# Nakuja.net
KiCad netlist of a schematic drawn in EasyEDA
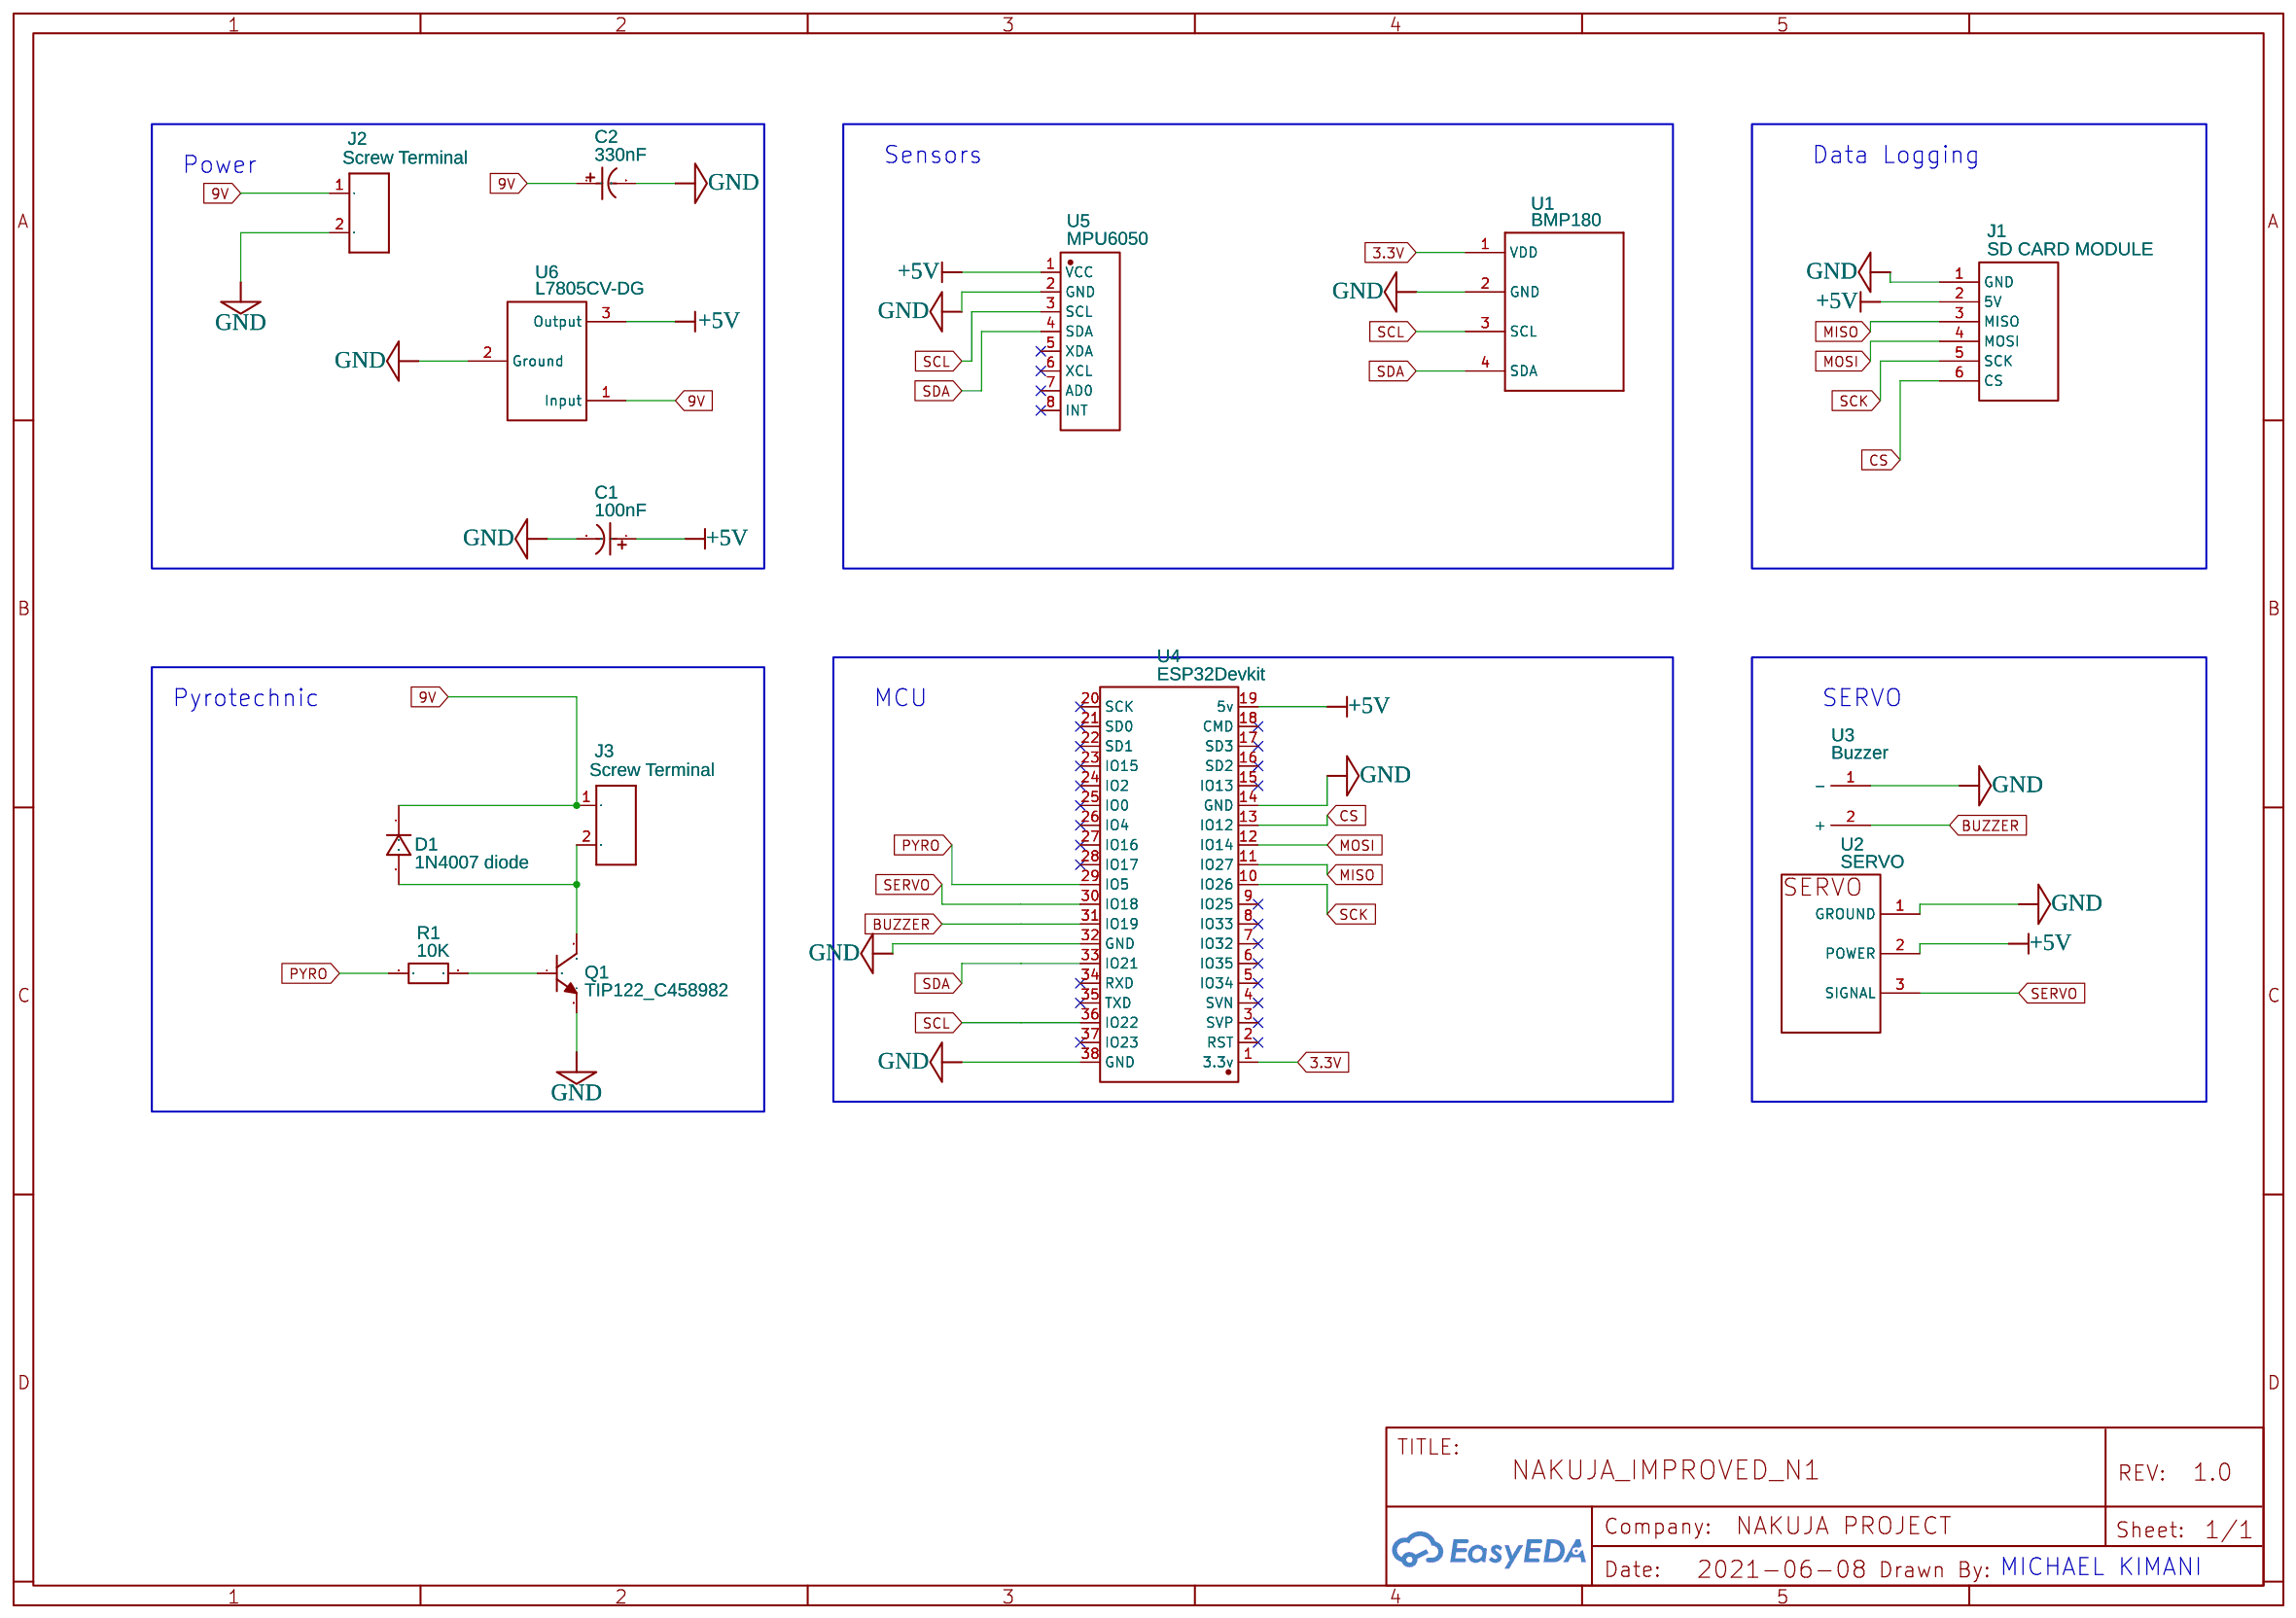
[diagram p0: schematic sheet]

(export (version "E")
  (design (tool "Eeschema 10.0.6"))
  (components
    (comp (ref "C1")
      (value "100nF")
      (fields (field (name "BOM_Manufacturer Part") "0.1UF 50V") (field (name "BOM_Supplier Part") "C28061"))
      (libsource (lib "") (part "0.1UF 50V"))
    )
    (comp (ref "C2")
      (value "330nF")
      (fields
        (field (name "BOM_Manufacturer Part") "0.33uF 50V 5*11")
        (field (name "BOM_Supplier Part") "C45097")
      )
      (libsource (lib "") (part "0.33uF 50V 5*11"))
    )
    (comp (ref "D1")
      (value "1N4007 diode")
      (fields (field (name "BOM_Manufacturer Part") "1N4007") (field (name "BOM_Supplier Part") "C331633"))
      (libsource (lib "") (part "1N4007 diode"))
    )
    (comp (ref "J1")
      (value "SD CARD MODULE")
      (fields (field (name "BOM_Manufacturer Part") "GREATZT 1pcs Micro SD card mini TF card reader module"))
      (libsource (lib "") (part "SD CARD MODULE"))
    )
    (comp (ref "J2")
      (value "Screw Terminal")
      (fields (field (name "BOM_Manufacturer Part") "?"))
      (libsource (lib "") (part "Screw Terminal"))
    )
    (comp (ref "J3")
      (value "Screw Terminal")
      (fields (field (name "BOM_Manufacturer Part") "?"))
      (libsource (lib "") (part "Screw Terminal"))
    )
    (comp (ref "Q1")
      (value "TIP122_C458982")
      (fields (field (name "BOM_Manufacturer Part") "TIP122") (field (name "BOM_Supplier Part") "C458982"))
      (libsource (lib "") (part "TIP122_C458982"))
    )
    (comp (ref "R1")
      (value "10K")
      (fields
        (field (name "BOM_Manufacturer Part") "RN 1/8W 10K F T/B A1")
        (field (name "BOM_Supplier Part") "C433502")
      )
      (libsource (lib "") (part "RN 1/8W 10K F T/B A1"))
    )
    (comp (ref "U1") (value "BMP180") (libsource (lib "") (part "BMP180")))
    (comp (ref "U2") (value "SERVO") (libsource (lib "") (part "SERVO")))
    (comp (ref "U3") (value "Buzzer") (libsource (lib "") (part "Buzzer")))
    (comp (ref "U4") (value "ESP32Devkit") (libsource (lib "") (part "ESP32Devkit")))
    (comp (ref "U5") (value "MPU6050") (libsource (lib "") (part "MPU6050")))
    (comp (ref "U6")
      (value "L7805CV-DG")
      (fields (field (name "BOM_Supplier Part") "C3795"))
      (libsource (lib "") (part "L7805CV-DG"))
    )
  )
  (nets
    (net (code "1") (name "+5V") (class "Default")
      (node (ref "C1") (pin "1") (pinfunction "1_1") (pintype "input"))
      (node (ref "J1") (pin "2") (pinfunction "5V_2") (pintype "unspecified"))
      (node (ref "U2") (pin "2") (pinfunction "POWER_2") (pintype "unspecified"))
      (node (ref "U4") (pin "19") (pinfunction "5v_19") (pintype "unspecified"))
      (node (ref "U5") (pin "1") (pinfunction "VCC_1") (pintype "unspecified"))
      (node (ref "U6") (pin "3") (pinfunction "Output_3") (pintype "unspecified"))
    )
    (net (code "2") (name "3.3V") (class "Default")
      (node (ref "U1") (pin "1") (pinfunction "VDD_1") (pintype "passive"))
      (node (ref "U4") (pin "1") (pinfunction "3.3v_1") (pintype "unspecified"))
    )
    (net (code "3") (name "9V") (class "Default")
      (node (ref "C2") (pin "1") (pinfunction "1_1") (pintype "input"))
      (node (ref "D1") (pin "1") (pinfunction "1_1") (pintype "unspecified"))
      (node (ref "J2") (pin "1") (pinfunction "1_1") (pintype "unspecified"))
      (node (ref "J3") (pin "1") (pinfunction "1_1") (pintype "unspecified"))
      (node (ref "U6") (pin "1") (pinfunction "Input_1") (pintype "unspecified"))
    )
    (net (code "4") (name "BUZZER") (class "Default")
      (node (ref "U3") (pin "2") (pinfunction "+_2") (pintype "unspecified"))
      (node (ref "U4") (pin "31") (pinfunction "IO19_31") (pintype "unspecified"))
    )
    (net (code "5") (name "CS") (class "Default")
      (node (ref "J1") (pin "6") (pinfunction "CS_6") (pintype "unspecified"))
      (node (ref "U4") (pin "13") (pinfunction "IO12_13") (pintype "unspecified"))
    )
    (net (code "6") (name "GND") (class "Default")
      (node (ref "C1") (pin "2") (pinfunction "2_2") (pintype "input"))
      (node (ref "C2") (pin "2") (pinfunction "2_2") (pintype "input"))
      (node (ref "J1") (pin "1") (pinfunction "GND_1") (pintype "unspecified"))
      (node (ref "J2") (pin "2") (pinfunction "2_2") (pintype "unspecified"))
      (node (ref "Q1") (pin "3") (pinfunction "E_3") (pintype "unspecified"))
      (node (ref "U1") (pin "2") (pinfunction "GND_2") (pintype "passive"))
      (node (ref "U2") (pin "1") (pinfunction "GROUND_1") (pintype "unspecified"))
      (node (ref "U3") (pin "1") (pinfunction "-_1") (pintype "unspecified"))
      (node (ref "U4") (pin "14") (pinfunction "GND_14") (pintype "unspecified"))
      (node (ref "U4") (pin "32") (pinfunction "GND_32") (pintype "unspecified"))
      (node (ref "U4") (pin "38") (pinfunction "GND_38") (pintype "unspecified"))
      (node (ref "U5") (pin "2") (pinfunction "GND_2") (pintype "unspecified"))
      (node (ref "U6") (pin "2") (pinfunction "Ground_2") (pintype "unspecified"))
    )
    (net (code "7") (name "MISO") (class "Default")
      (node (ref "J1") (pin "3") (pinfunction "MISO_3") (pintype "unspecified"))
      (node (ref "U4") (pin "11") (pinfunction "IO27_11") (pintype "unspecified"))
    )
    (net (code "8") (name "MOSI") (class "Default")
      (node (ref "J1") (pin "4") (pinfunction "MOSI_4") (pintype "unspecified"))
      (node (ref "U4") (pin "12") (pinfunction "IO14_12") (pintype "unspecified"))
    )
    (net (code "9") (name "Net-(Q1-B)") (class "Default")
      (node (ref "Q1") (pin "1") (pinfunction "B_1") (pintype "unspecified"))
      (node (ref "R1") (pin "1") (pinfunction "1_1") (pintype "unspecified"))
    )
    (net (code "10") (name "Net-(Q1-C)") (class "Default")
      (node (ref "D1") (pin "2") (pinfunction "2_2") (pintype "unspecified"))
      (node (ref "J3") (pin "2") (pinfunction "2_2") (pintype "unspecified"))
      (node (ref "Q1") (pin "2") (pinfunction "C_2") (pintype "unspecified"))
    )
    (net (code "11") (name "PYRO") (class "Default")
      (node (ref "R1") (pin "2") (pinfunction "2_2") (pintype "unspecified"))
      (node (ref "U4") (pin "29") (pinfunction "IO5_29") (pintype "unspecified"))
    )
    (net (code "12") (name "SCK") (class "Default")
      (node (ref "J1") (pin "5") (pinfunction "SCK_5") (pintype "unspecified"))
      (node (ref "U4") (pin "10") (pinfunction "IO26_10") (pintype "unspecified"))
    )
    (net (code "13") (name "SCL") (class "Default")
      (node (ref "U1") (pin "3") (pinfunction "SCL_3") (pintype "input"))
      (node (ref "U4") (pin "36") (pinfunction "IO22_36") (pintype "unspecified"))
      (node (ref "U5") (pin "3") (pinfunction "SCL_3") (pintype "unspecified"))
    )
    (net (code "14") (name "SDA") (class "Default")
      (node (ref "U1") (pin "4") (pinfunction "SDA_4") (pintype "unspecified"))
      (node (ref "U4") (pin "33") (pinfunction "IO21_33") (pintype "unspecified"))
      (node (ref "U5") (pin "4") (pinfunction "SDA_4") (pintype "unspecified"))
    )
    (net (code "15") (name "SERVO") (class "Default")
      (node (ref "U2") (pin "3") (pinfunction "SIGNAL_3") (pintype "unspecified"))
      (node (ref "U4") (pin "30") (pinfunction "IO18_30") (pintype "unspecified"))
    )
    (net (code "16") (name "unconnected-(U4-CMD-Pad18)") (class "Default")
      (node (ref "U4") (pin "18") (pinfunction "CMD_18") (pintype "unspecified+no_connect"))
    )
    (net (code "17") (name "unconnected-(U4-IO0-Pad25)") (class "Default")
      (node (ref "U4") (pin "25") (pinfunction "IO0_25") (pintype "unspecified+no_connect"))
    )
    (net (code "18") (name "unconnected-(U4-IO2-Pad24)") (class "Default")
      (node (ref "U4") (pin "24") (pinfunction "IO2_24") (pintype "unspecified+no_connect"))
    )
    (net (code "19") (name "unconnected-(U4-IO4-Pad26)") (class "Default")
      (node (ref "U4") (pin "26") (pinfunction "IO4_26") (pintype "unspecified+no_connect"))
    )
    (net (code "20") (name "unconnected-(U4-IO13-Pad15)") (class "Default")
      (node (ref "U4") (pin "15") (pinfunction "IO13_15") (pintype "unspecified+no_connect"))
    )
    (net (code "21") (name "unconnected-(U4-IO15-Pad23)") (class "Default")
      (node (ref "U4") (pin "23") (pinfunction "IO15_23") (pintype "unspecified+no_connect"))
    )
    (net (code "22") (name "unconnected-(U4-IO16-Pad27)") (class "Default")
      (node (ref "U4") (pin "27") (pinfunction "IO16_27") (pintype "unspecified+no_connect"))
    )
    (net (code "23") (name "unconnected-(U4-IO17-Pad28)") (class "Default")
      (node (ref "U4") (pin "28") (pinfunction "IO17_28") (pintype "unspecified+no_connect"))
    )
    (net (code "24") (name "unconnected-(U4-IO23-Pad37)") (class "Default")
      (node (ref "U4") (pin "37") (pinfunction "IO23_37") (pintype "unspecified+no_connect"))
    )
    (net (code "25") (name "unconnected-(U4-IO25-Pad9)") (class "Default")
      (node (ref "U4") (pin "9") (pinfunction "IO25_9") (pintype "unspecified+no_connect"))
    )
    (net (code "26") (name "unconnected-(U4-IO32-Pad7)") (class "Default")
      (node (ref "U4") (pin "7") (pinfunction "IO32_7") (pintype "unspecified+no_connect"))
    )
    (net (code "27") (name "unconnected-(U4-IO33-Pad8)") (class "Default")
      (node (ref "U4") (pin "8") (pinfunction "IO33_8") (pintype "unspecified+no_connect"))
    )
    (net (code "28") (name "unconnected-(U4-IO34-Pad5)") (class "Default")
      (node (ref "U4") (pin "5") (pinfunction "IO34_5") (pintype "unspecified+no_connect"))
    )
    (net (code "29") (name "unconnected-(U4-IO35-Pad6)") (class "Default")
      (node (ref "U4") (pin "6") (pinfunction "IO35_6") (pintype "unspecified+no_connect"))
    )
    (net (code "30") (name "unconnected-(U4-RST-Pad2)") (class "Default")
      (node (ref "U4") (pin "2") (pinfunction "RST_2") (pintype "unspecified+no_connect"))
    )
    (net (code "31") (name "unconnected-(U4-RXD-Pad34)") (class "Default")
      (node (ref "U4") (pin "34") (pinfunction "RXD_34") (pintype "unspecified+no_connect"))
    )
    (net (code "32") (name "unconnected-(U4-SCK-Pad20)") (class "Default")
      (node (ref "U4") (pin "20") (pinfunction "SCK_20") (pintype "unspecified+no_connect"))
    )
    (net (code "33") (name "unconnected-(U4-SD0-Pad21)") (class "Default")
      (node (ref "U4") (pin "21") (pinfunction "SD0_21") (pintype "unspecified+no_connect"))
    )
    (net (code "34") (name "unconnected-(U4-SD1-Pad22)") (class "Default")
      (node (ref "U4") (pin "22") (pinfunction "SD1_22") (pintype "unspecified+no_connect"))
    )
    (net (code "35") (name "unconnected-(U4-SD2-Pad16)") (class "Default")
      (node (ref "U4") (pin "16") (pinfunction "SD2_16") (pintype "unspecified+no_connect"))
    )
    (net (code "36") (name "unconnected-(U4-SD3-Pad17)") (class "Default")
      (node (ref "U4") (pin "17") (pinfunction "SD3_17") (pintype "unspecified+no_connect"))
    )
    (net (code "37") (name "unconnected-(U4-SVN-Pad4)") (class "Default")
      (node (ref "U4") (pin "4") (pinfunction "SVN_4") (pintype "unspecified+no_connect"))
    )
    (net (code "38") (name "unconnected-(U4-SVP-Pad3)") (class "Default")
      (node (ref "U4") (pin "3") (pinfunction "SVP_3") (pintype "unspecified+no_connect"))
    )
    (net (code "39") (name "unconnected-(U4-TXD-Pad35)") (class "Default")
      (node (ref "U4") (pin "35") (pinfunction "TXD_35") (pintype "unspecified+no_connect"))
    )
    (net (code "40") (name "unconnected-(U5-AD0-Pad7)") (class "Default")
      (node (ref "U5") (pin "7") (pinfunction "AD0_7") (pintype "unspecified+no_connect"))
    )
    (net (code "41") (name "unconnected-(U5-INT-Pad8)") (class "Default")
      (node (ref "U5") (pin "8") (pinfunction "INT_8") (pintype "unspecified+no_connect"))
    )
    (net (code "42") (name "unconnected-(U5-XCL-Pad6)") (class "Default")
      (node (ref "U5") (pin "6") (pinfunction "XCL_6") (pintype "unspecified+no_connect"))
    )
    (net (code "43") (name "unconnected-(U5-XDA-Pad5)") (class "Default")
      (node (ref "U5") (pin "5") (pinfunction "XDA_5") (pintype "unspecified+no_connect"))
    )
  )
)
